# Indicators.net
KiCad netlist of a schematic drawn in Altium Designer
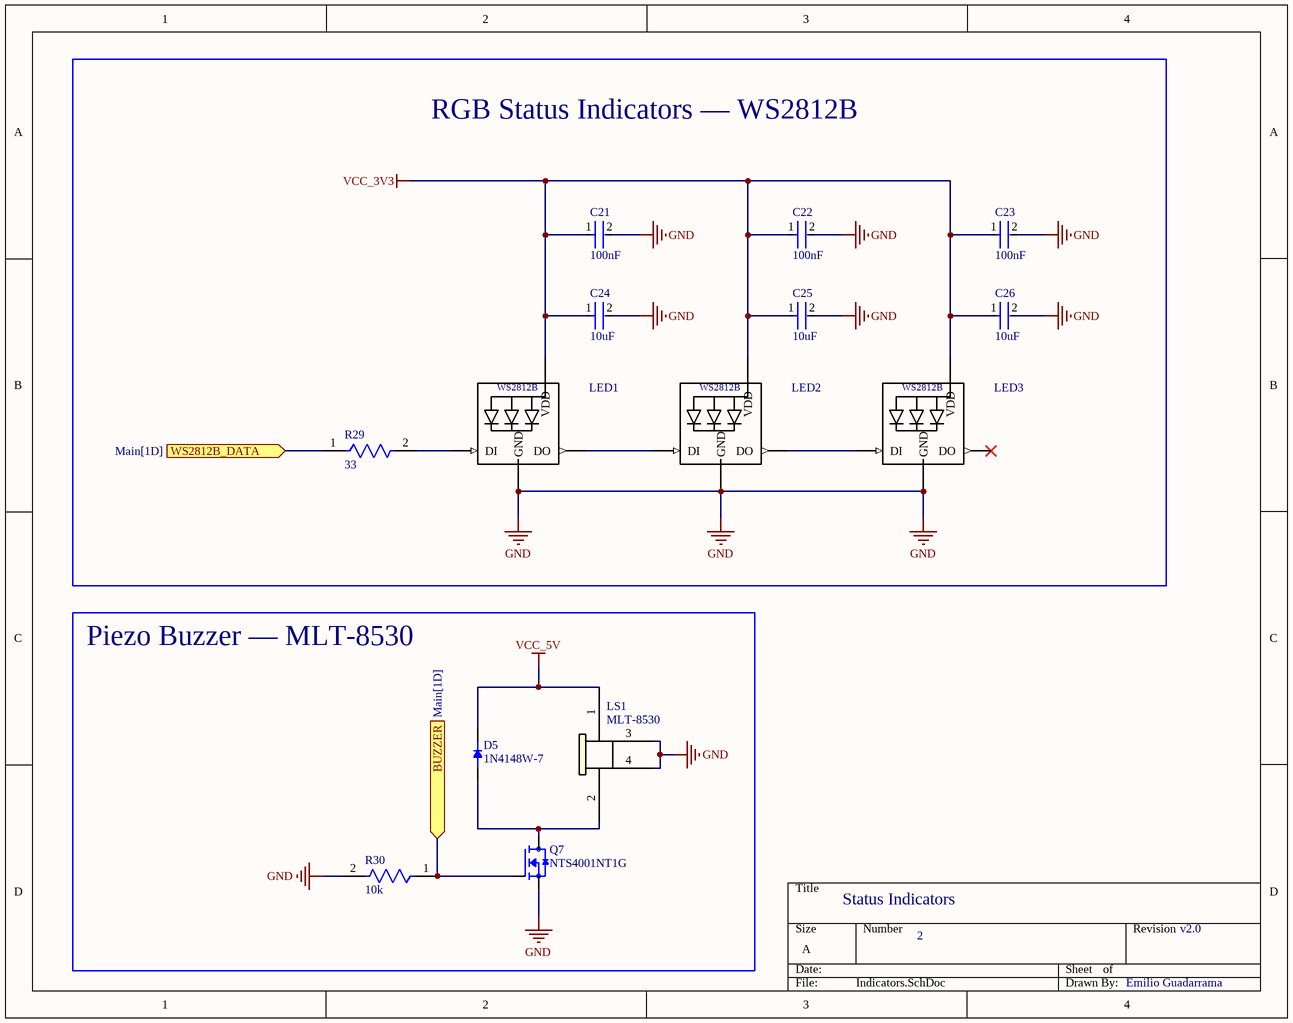
[diagram p0: Indicators.SchDoc]

(export (version "E")
  (design (tool "Eeschema 10.0.6"))
  (components
    (comp (ref "C21")
      (value "100nF")
      (footprint "FP-C0805C-DN-MFG")
      (description "CAP CER 0.1UF 50V X7R 0805")
      (fields
        (field (name "MANUFACTURER PART NUMBER") "C0805C104K5RACTU")
        (field (name "MANUFACTURER") "KEMET")
      )
      (libsource (lib "Altium Content Vault") (part "b4654b650e69147ec39a6b967a45e02"))
    )
    (comp (ref "C22")
      (value "100nF")
      (footprint "FP-C0805C-DN-MFG")
      (description "CAP CER 0.1UF 50V X7R 0805")
      (fields
        (field (name "MANUFACTURER PART NUMBER") "C0805C104K5RACTU")
        (field (name "MANUFACTURER") "KEMET")
      )
      (libsource (lib "Altium Content Vault") (part "b4654b650e69147ec39a6b967a45e02"))
    )
    (comp (ref "C23")
      (value "100nF")
      (footprint "FP-C0805C-DN-MFG")
      (description "CAP CER 0.1UF 50V X7R 0805")
      (fields
        (field (name "MANUFACTURER PART NUMBER") "C0805C104K5RACTU")
        (field (name "MANUFACTURER") "KEMET")
      )
      (libsource (lib "Altium Content Vault") (part "b4654b650e69147ec39a6b967a45e02"))
    )
    (comp (ref "C24")
      (value "10uF")
      (footprint "FP-C0805C-DN-MFG")
      (description "CAP CER 0.1UF 50V X7R 0805")
      (fields
        (field (name "MANUFACTURER PART NUMBER") "C0805C104K5RACTU")
        (field (name "MANUFACTURER") "KEMET")
      )
      (libsource (lib "Altium Content Vault") (part "b4654b650e69147ec39a6b967a45e02"))
    )
    (comp (ref "C25")
      (value "10uF")
      (footprint "FP-C0805C-DN-MFG")
      (description "CAP CER 0.1UF 50V X7R 0805")
      (fields
        (field (name "MANUFACTURER PART NUMBER") "C0805C104K5RACTU")
        (field (name "MANUFACTURER") "KEMET")
      )
      (libsource (lib "Altium Content Vault") (part "b4654b650e69147ec39a6b967a45e02"))
    )
    (comp (ref "C26")
      (value "10uF")
      (footprint "FP-C0805C-DN-MFG")
      (description "CAP CER 0.1UF 50V X7R 0805")
      (fields
        (field (name "MANUFACTURER PART NUMBER") "C0805C104K5RACTU")
        (field (name "MANUFACTURER") "KEMET")
      )
      (libsource (lib "Altium Content Vault") (part "b4654b650e69147ec39a6b967a45e02"))
    )
    (comp (ref "D5")
      (value "1N4148W-7")
      (footprint "SOD3715X135N")
      (description "Diode Standard 100 V 300mA (DC) Surface Mount SOD-123")
      (fields (field (name "MF") "Diodes Inc."))
      (libsource (lib "1N4148W-7") (part "1N4148W-7"))
    )
    (comp (ref "LED1")
      (value "WS2812B")
      (footprint "*LED3535")
      (description "Intelligent control LED integrated light source")
      (fields (field (name "MF") "Worldsemi"))
      (libsource (lib "LED_RGB_WS2812B") (part "WS2812B"))
    )
    (comp (ref "LED2")
      (value "WS2812B")
      (footprint "*LED3535")
      (description "Intelligent control LED integrated light source")
      (fields (field (name "MF") "Worldsemi"))
      (libsource (lib "LED_RGB_WS2812B") (part "WS2812B"))
    )
    (comp (ref "LED3")
      (value "WS2812B")
      (footprint "*LED3535")
      (description "Intelligent control LED integrated light source")
      (fields (field (name "MF") "Worldsemi"))
      (libsource (lib "LED_RGB_WS2812B") (part "WS2812B"))
    )
    (comp (ref "LS1")
      (value "MLT-8530")
      (footprint "MLT-8530_JHE")
      (description "Description")
      (fields (field (name "COPYRIGHT") "Copyright (C) 2025 Ultra Librarian. All rights reserved."))
      (libsource (lib "MLT-8530") (part "MLT-8530"))
    )
    (comp (ref "Q7")
      (value "NTS4001NT1G")
      (footprint "SOT65P220X100-3N")
      (description "N-Channel 30V 270mA _Ta_ 330mW _Ta_ Surface Mount SC-70-3 _SOT323_")
      (fields (field (name "MF") "ON Semiconductor"))
      (libsource (lib "NTS4001NT1G") (part "NTS4001NT1G"))
    )
    (comp (ref "R29")
      (value "33")
      (footprint "FP-MCT0603-IPC_A")
      (description "RES SMD 100 OHM 1% 1/8W 0603")
      (fields (field (name "TOLERANCE") "0.1%"))
      (libsource (lib "Altium Content Vault") (part "1029c3af85768c4190bb7ad29bc67b5"))
    )
    (comp (ref "R30")
      (value "10k")
      (footprint "FP-MCT0603-IPC_A")
      (description "RES SMD 100 OHM 1% 1/8W 0603")
      (fields (field (name "TOLERANCE") "0.1%"))
      (libsource (lib "Altium Content Vault") (part "1029c3af85768c4190bb7ad29bc67b5"))
    )
  )
  (nets
    (net (code "1") (name "/BUZZER") (class "Default")
      (node (ref "Q7") (pin "1") (pinfunction "G_1") (pintype "passive"))
      (node (ref "R30") (pin "1") (pinfunction "1_1") (pintype "passive"))
    )
    (net (code "2") (name "/WS2812B_DATA") (class "Default")
      (node (ref "R29") (pin "1") (pinfunction "1_1") (pintype "passive"))
    )
    (net (code "3") (name "GND") (class "Default")
      (node (ref "C21") (pin "2") (pinfunction "2_2") (pintype "passive"))
      (node (ref "C22") (pin "2") (pinfunction "2_2") (pintype "passive"))
      (node (ref "C23") (pin "2") (pinfunction "2_2") (pintype "passive"))
      (node (ref "C24") (pin "2") (pinfunction "2_2") (pintype "passive"))
      (node (ref "C25") (pin "2") (pinfunction "2_2") (pintype "passive"))
      (node (ref "C26") (pin "2") (pinfunction "2_2") (pintype "passive"))
      (node (ref "LED1") (pin "3") (pinfunction "GND_3") (pintype "power_in"))
      (node (ref "LED2") (pin "3") (pinfunction "GND_3") (pintype "power_in"))
      (node (ref "LED3") (pin "3") (pinfunction "GND_3") (pintype "power_in"))
      (node (ref "LS1") (pin "3") (pinfunction "3_3") (pintype "passive"))
      (node (ref "LS1") (pin "4") (pinfunction "4_4") (pintype "passive"))
      (node (ref "Q7") (pin "2") (pinfunction "S_2") (pintype "passive"))
      (node (ref "R30") (pin "2") (pinfunction "2_2") (pintype "passive"))
    )
    (net (code "4") (name "Net-(LED1-DI)") (class "Default")
      (node (ref "LED1") (pin "4") (pinfunction "DI_4") (pintype "input"))
      (node (ref "R29") (pin "2") (pinfunction "2_2") (pintype "passive"))
    )
    (net (code "5") (name "Net-(LED1-DO)") (class "Default")
      (node (ref "LED1") (pin "2") (pinfunction "DO_2") (pintype "output"))
      (node (ref "LED2") (pin "4") (pinfunction "DI_4") (pintype "input"))
    )
    (net (code "6") (name "Net-(LED2-DO)") (class "Default")
      (node (ref "LED2") (pin "2") (pinfunction "DO_2") (pintype "output"))
      (node (ref "LED3") (pin "4") (pinfunction "DI_4") (pintype "input"))
    )
    (net (code "7") (name "Net-(Q7-D)") (class "Default")
      (node (ref "D5") (pin "A") (pinfunction "A_A") (pintype "passive"))
      (node (ref "LS1") (pin "2") (pinfunction "2_2") (pintype "passive"))
      (node (ref "Q7") (pin "3") (pinfunction "D_3") (pintype "passive"))
    )
    (net (code "8") (name "VCC_3V3") (class "Default")
      (node (ref "C21") (pin "1") (pinfunction "1_1") (pintype "passive"))
      (node (ref "C22") (pin "1") (pinfunction "1_1") (pintype "passive"))
      (node (ref "C23") (pin "1") (pinfunction "1_1") (pintype "passive"))
      (node (ref "C24") (pin "1") (pinfunction "1_1") (pintype "passive"))
      (node (ref "C25") (pin "1") (pinfunction "1_1") (pintype "passive"))
      (node (ref "C26") (pin "1") (pinfunction "1_1") (pintype "passive"))
      (node (ref "LED1") (pin "1") (pinfunction "VDD_1") (pintype "power_in"))
      (node (ref "LED2") (pin "1") (pinfunction "VDD_1") (pintype "power_in"))
      (node (ref "LED3") (pin "1") (pinfunction "VDD_1") (pintype "power_in"))
    )
    (net (code "9") (name "VCC_5V") (class "Default")
      (node (ref "D5") (pin "C") (pinfunction "K_C") (pintype "passive"))
      (node (ref "LS1") (pin "1") (pinfunction "1_1") (pintype "passive"))
    )
    (net (code "10") (name "unconnected-(LED3-DO-Pad2)") (class "Default")
      (node (ref "LED3") (pin "2") (pinfunction "DO_2") (pintype "output+no_connect"))
    )
  )
)
